# p1s.net
KiCad netlist of a schematic drawn in EAGLE
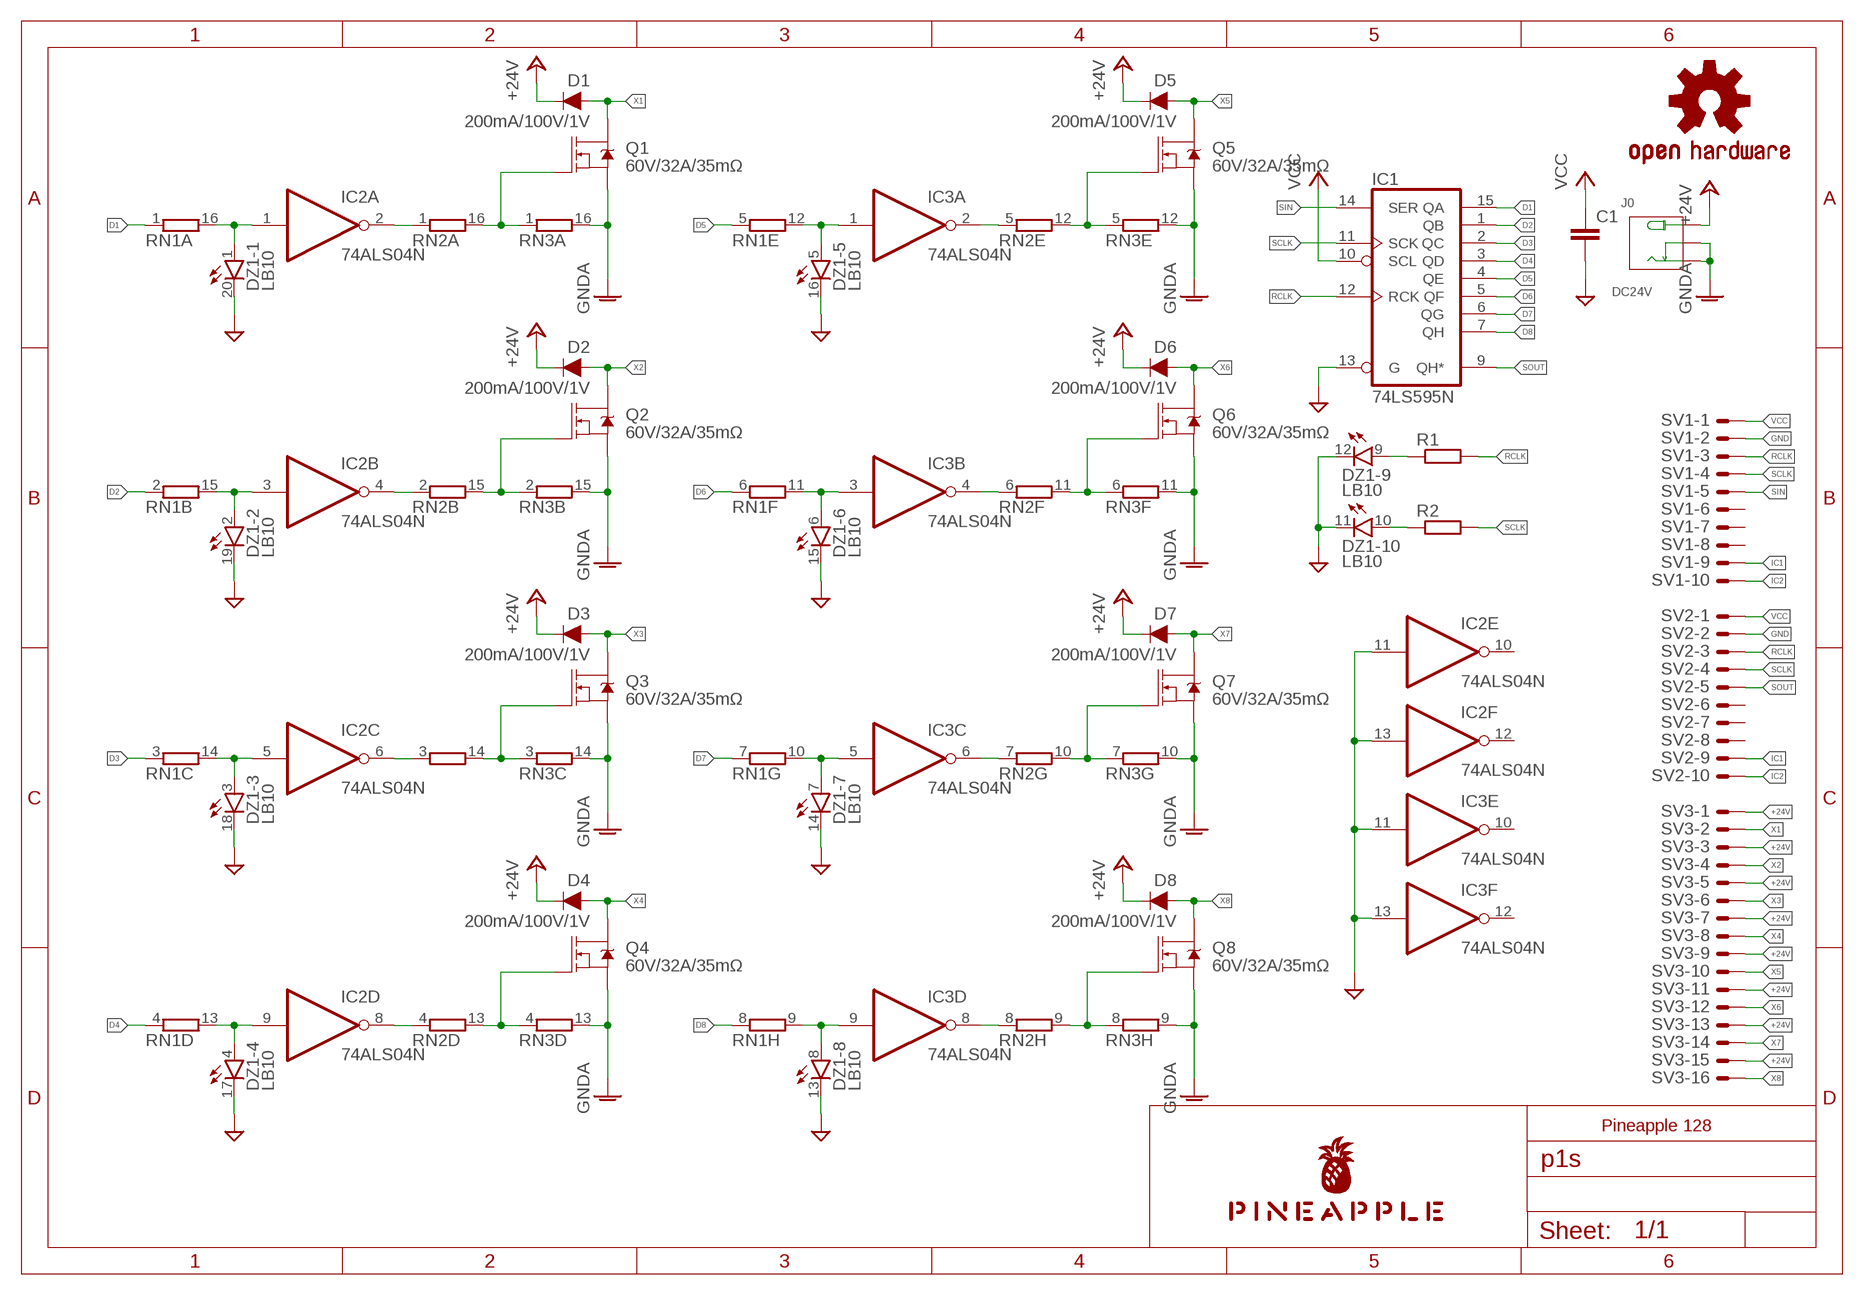
[diagram p0: schematic, sheet 1]

(export (version "E")
  (design (tool "Eeschema 10.0.6"))
  (components
    (comp (ref "C1")
      (value "C-EU025-024X044")
      (footprint "eagle-import:C025-024X044")
      (libsource (lib "eagle-import") (part "C-EU025-024X044"))
    )
    (comp (ref "D1")
      (value "200mA/100V/1V")
      (footprint "eagle-import:DIODE-1N4148")
      (libsource (lib "eagle-import") (part "DIODE-1N4148"))
    )
    (comp (ref "D2")
      (value "200mA/100V/1V")
      (footprint "eagle-import:DIODE-1N4148")
      (libsource (lib "eagle-import") (part "DIODE-1N4148"))
    )
    (comp (ref "D3")
      (value "200mA/100V/1V")
      (footprint "eagle-import:DIODE-1N4148")
      (libsource (lib "eagle-import") (part "DIODE-1N4148"))
    )
    (comp (ref "D4")
      (value "200mA/100V/1V")
      (footprint "eagle-import:DIODE-1N4148")
      (libsource (lib "eagle-import") (part "DIODE-1N4148"))
    )
    (comp (ref "D5")
      (value "200mA/100V/1V")
      (footprint "eagle-import:DIODE-1N4148")
      (libsource (lib "eagle-import") (part "DIODE-1N4148"))
    )
    (comp (ref "D6")
      (value "200mA/100V/1V")
      (footprint "eagle-import:DIODE-1N4148")
      (libsource (lib "eagle-import") (part "DIODE-1N4148"))
    )
    (comp (ref "D7")
      (value "200mA/100V/1V")
      (footprint "eagle-import:DIODE-1N4148")
      (libsource (lib "eagle-import") (part "DIODE-1N4148"))
    )
    (comp (ref "D8")
      (value "200mA/100V/1V")
      (footprint "eagle-import:DIODE-1N4148")
      (libsource (lib "eagle-import") (part "DIODE-1N4148"))
    )
    (comp (ref "DZ1")
      (value "LB10")
      (footprint "eagle-import:LB10")
      (libsource (lib "eagle-import") (part "LB10"))
    )
    (comp (ref "IC1")
      (value "74LS595N")
      (footprint "eagle-import:DIL16")
      (libsource (lib "eagle-import") (part "74595NLS"))
    )
    (comp (ref "IC2")
      (value "74ALS04N")
      (footprint "eagle-import:DIL14")
      (libsource (lib "eagle-import") (part "7404NALS"))
    )
    (comp (ref "IC3")
      (value "74ALS04N")
      (footprint "eagle-import:DIL14")
      (libsource (lib "eagle-import") (part "7404NALS"))
    )
    (comp (ref "J0")
      (value "DC24V")
      (footprint "eagle-import:3P-L14.2_W11.0_H9.0MM")
      (libsource (lib "eagle-import") (part "JACK-DC-005'DC-005'"))
    )
    (comp (ref "LOGO1")
      (value "OSHW-LOGOS-COPPER")
      (footprint "eagle-import:OSHW-LOGO-S_COPPER")
      (libsource (lib "eagle-import") (part "OSHW-LOGOS-COPPER"))
    )
    (comp (ref "Q1")
      (value "60V/32A/35mΩ")
      (footprint "eagle-import:TO220V")
      (libsource (lib "eagle-import") (part "MOSFET-NCH-FQP30N06L"))
    )
    (comp (ref "Q2")
      (value "60V/32A/35mΩ")
      (footprint "eagle-import:TO220V")
      (libsource (lib "eagle-import") (part "MOSFET-NCH-FQP30N06L"))
    )
    (comp (ref "Q3")
      (value "60V/32A/35mΩ")
      (footprint "eagle-import:TO220V")
      (libsource (lib "eagle-import") (part "MOSFET-NCH-FQP30N06L"))
    )
    (comp (ref "Q4")
      (value "60V/32A/35mΩ")
      (footprint "eagle-import:TO220V")
      (libsource (lib "eagle-import") (part "MOSFET-NCH-FQP30N06L"))
    )
    (comp (ref "Q5")
      (value "60V/32A/35mΩ")
      (footprint "eagle-import:TO220V")
      (libsource (lib "eagle-import") (part "MOSFET-NCH-FQP30N06L"))
    )
    (comp (ref "Q6")
      (value "60V/32A/35mΩ")
      (footprint "eagle-import:TO220V")
      (libsource (lib "eagle-import") (part "MOSFET-NCH-FQP30N06L"))
    )
    (comp (ref "Q7")
      (value "60V/32A/35mΩ")
      (footprint "eagle-import:TO220V")
      (libsource (lib "eagle-import") (part "MOSFET-NCH-FQP30N06L"))
    )
    (comp (ref "Q8")
      (value "60V/32A/35mΩ")
      (footprint "eagle-import:TO220V")
      (libsource (lib "eagle-import") (part "MOSFET-NCH-FQP30N06L"))
    )
    (comp (ref "R1")
      (value "R-EU_0204/5")
      (footprint "eagle-import:0204_5")
      (libsource (lib "eagle-import") (part "R-EU_0204/5"))
    )
    (comp (ref "R2")
      (value "R-EU_0204/5")
      (footprint "eagle-import:0204_5")
      (libsource (lib "eagle-import") (part "R-EU_0204/5"))
    )
    (comp (ref "RN1")
      (value "8R-N")
      (footprint "eagle-import:DIL16")
      (libsource (lib "eagle-import") (part "8R-N"))
    )
    (comp (ref "RN2")
      (value "8R-N")
      (footprint "eagle-import:DIL16")
      (libsource (lib "eagle-import") (part "8R-N"))
    )
    (comp (ref "RN3")
      (value "8R-N")
      (footprint "eagle-import:DIL16")
      (libsource (lib "eagle-import") (part "8R-N"))
    )
    (comp (ref "SV1")
      (value "ML10LE")
      (footprint "eagle-import:ML10L")
      (libsource (lib "eagle-import") (part "ML10LE"))
    )
    (comp (ref "SV2")
      (value "ML10LE")
      (footprint "eagle-import:ML10L")
      (libsource (lib "eagle-import") (part "ML10LE"))
    )
    (comp (ref "SV3")
      (value "ML16LE")
      (footprint "eagle-import:ML16L")
      (libsource (lib "eagle-import") (part "ML16LE"))
    )
    (comp (ref "U$1")
      (value "PINEAPPLE450_SILK")
      (footprint "eagle-import:PINEAPPLE450_SILK")
      (libsource (lib "eagle-import") (part "PINEAPPLE450_SILK"))
    )
  )
  (nets
    (net (code "1") (name "+24V") (class "Default")
      (node (ref "D1") (pin "C") (pinfunction "C_C") (pintype "passive"))
      (node (ref "D2") (pin "C") (pinfunction "C_C") (pintype "passive"))
      (node (ref "D3") (pin "C") (pinfunction "C_C") (pintype "passive"))
      (node (ref "D4") (pin "C") (pinfunction "C_C") (pintype "passive"))
      (node (ref "D5") (pin "C") (pinfunction "C_C") (pintype "passive"))
      (node (ref "D6") (pin "C") (pinfunction "C_C") (pintype "passive"))
      (node (ref "D7") (pin "C") (pinfunction "C_C") (pintype "passive"))
      (node (ref "D8") (pin "C") (pinfunction "C_C") (pintype "passive"))
      (node (ref "J0") (pin "+") (pinfunction "+_+") (pintype "bidirectional"))
      (node (ref "SV3") (pin "1") (pinfunction "S_1") (pintype "passive"))
      (node (ref "SV3") (pin "11") (pinfunction "S_11") (pintype "passive"))
      (node (ref "SV3") (pin "13") (pinfunction "S_13") (pintype "passive"))
      (node (ref "SV3") (pin "15") (pinfunction "S_15") (pintype "passive"))
      (node (ref "SV3") (pin "3") (pinfunction "S_3") (pintype "passive"))
      (node (ref "SV3") (pin "5") (pinfunction "S_5") (pintype "passive"))
      (node (ref "SV3") (pin "7") (pinfunction "S_7") (pintype "passive"))
      (node (ref "SV3") (pin "9") (pinfunction "S_9") (pintype "passive"))
    )
    (net (code "2") (name "D1") (class "Default")
      (node (ref "IC1") (pin "15") (pinfunction "QA_15") (pintype "tri_state"))
      (node (ref "RN1") (pin "1") (pinfunction "1_1") (pintype "passive"))
    )
    (net (code "3") (name "D2") (class "Default")
      (node (ref "IC1") (pin "1") (pinfunction "QB_1") (pintype "tri_state"))
      (node (ref "RN1") (pin "2") (pinfunction "1_2") (pintype "passive"))
    )
    (net (code "4") (name "D3") (class "Default")
      (node (ref "IC1") (pin "2") (pinfunction "QC_2") (pintype "tri_state"))
      (node (ref "RN1") (pin "3") (pinfunction "1_3") (pintype "passive"))
    )
    (net (code "5") (name "D4") (class "Default")
      (node (ref "IC1") (pin "3") (pinfunction "QD_3") (pintype "tri_state"))
      (node (ref "RN1") (pin "4") (pinfunction "1_4") (pintype "passive"))
    )
    (net (code "6") (name "D5") (class "Default")
      (node (ref "IC1") (pin "4") (pinfunction "QE_4") (pintype "tri_state"))
      (node (ref "RN1") (pin "5") (pinfunction "1_5") (pintype "passive"))
    )
    (net (code "7") (name "D6") (class "Default")
      (node (ref "IC1") (pin "5") (pinfunction "QF_5") (pintype "tri_state"))
      (node (ref "RN1") (pin "6") (pinfunction "1_6") (pintype "passive"))
    )
    (net (code "8") (name "D7") (class "Default")
      (node (ref "IC1") (pin "6") (pinfunction "QG_6") (pintype "tri_state"))
      (node (ref "RN1") (pin "7") (pinfunction "1_7") (pintype "passive"))
    )
    (net (code "9") (name "D8") (class "Default")
      (node (ref "IC1") (pin "7") (pinfunction "QH_7") (pintype "tri_state"))
      (node (ref "RN1") (pin "8") (pinfunction "1_8") (pintype "passive"))
    )
    (net (code "10") (name "GND") (class "Default")
      (node (ref "C1") (pin "2") (pinfunction "2_2") (pintype "passive"))
      (node (ref "DZ1") (pin "11") (pinfunction "C_11") (pintype "passive"))
      (node (ref "DZ1") (pin "12") (pinfunction "C_12") (pintype "passive"))
      (node (ref "DZ1") (pin "13") (pinfunction "C_13") (pintype "passive"))
      (node (ref "DZ1") (pin "14") (pinfunction "C_14") (pintype "passive"))
      (node (ref "DZ1") (pin "15") (pinfunction "C_15") (pintype "passive"))
      (node (ref "DZ1") (pin "16") (pinfunction "C_16") (pintype "passive"))
      (node (ref "DZ1") (pin "17") (pinfunction "C_17") (pintype "passive"))
      (node (ref "DZ1") (pin "18") (pinfunction "C_18") (pintype "passive"))
      (node (ref "DZ1") (pin "19") (pinfunction "C_19") (pintype "passive"))
      (node (ref "DZ1") (pin "20") (pinfunction "C_20") (pintype "passive"))
      (node (ref "IC1") (pin "13") (pinfunction "G_13") (pintype "input"))
      (node (ref "IC2") (pin "11") (pinfunction "I_11") (pintype "input"))
      (node (ref "IC2") (pin "13") (pinfunction "I_13") (pintype "input"))
      (node (ref "IC3") (pin "11") (pinfunction "I_11") (pintype "input"))
      (node (ref "IC3") (pin "13") (pinfunction "I_13") (pintype "input"))
      (node (ref "SV1") (pin "2") (pinfunction "S_2") (pintype "passive"))
      (node (ref "SV2") (pin "2") (pinfunction "S_2") (pintype "passive"))
    )
    (net (code "11") (name "GNDA") (class "Default")
      (node (ref "J0") (pin "-1") (pinfunction "-_-1") (pintype "bidirectional"))
      (node (ref "J0") (pin "-2") (pinfunction "CDN_-2") (pintype "bidirectional"))
      (node (ref "Q1") (pin "3") (pinfunction "S_3") (pintype "bidirectional"))
      (node (ref "Q2") (pin "3") (pinfunction "S_3") (pintype "bidirectional"))
      (node (ref "Q3") (pin "3") (pinfunction "S_3") (pintype "bidirectional"))
      (node (ref "Q4") (pin "3") (pinfunction "S_3") (pintype "bidirectional"))
      (node (ref "Q5") (pin "3") (pinfunction "S_3") (pintype "bidirectional"))
      (node (ref "Q6") (pin "3") (pinfunction "S_3") (pintype "bidirectional"))
      (node (ref "Q7") (pin "3") (pinfunction "S_3") (pintype "bidirectional"))
      (node (ref "Q8") (pin "3") (pinfunction "S_3") (pintype "bidirectional"))
      (node (ref "RN3") (pin "10") (pinfunction "2_10") (pintype "passive"))
      (node (ref "RN3") (pin "11") (pinfunction "2_11") (pintype "passive"))
      (node (ref "RN3") (pin "12") (pinfunction "2_12") (pintype "passive"))
      (node (ref "RN3") (pin "13") (pinfunction "2_13") (pintype "passive"))
      (node (ref "RN3") (pin "14") (pinfunction "2_14") (pintype "passive"))
      (node (ref "RN3") (pin "15") (pinfunction "2_15") (pintype "passive"))
      (node (ref "RN3") (pin "16") (pinfunction "2_16") (pintype "passive"))
      (node (ref "RN3") (pin "9") (pinfunction "2_9") (pintype "passive"))
    )
    (net (code "12") (name "IC1") (class "Default")
      (node (ref "SV1") (pin "9") (pinfunction "S_9") (pintype "passive"))
      (node (ref "SV2") (pin "9") (pinfunction "S_9") (pintype "passive"))
    )
    (net (code "13") (name "IC2") (class "Default")
      (node (ref "SV1") (pin "10") (pinfunction "S_10") (pintype "passive"))
      (node (ref "SV2") (pin "10") (pinfunction "S_10") (pintype "passive"))
    )
    (net (code "14") (name "Net-(DZ1A-A)") (class "Default")
      (node (ref "DZ1") (pin "1") (pinfunction "A_1") (pintype "passive"))
      (node (ref "IC2") (pin "1") (pinfunction "I_1") (pintype "input"))
      (node (ref "RN1") (pin "16") (pinfunction "2_16") (pintype "passive"))
    )
    (net (code "15") (name "Net-(DZ1B-A)") (class "Default")
      (node (ref "DZ1") (pin "10") (pinfunction "A_10") (pintype "passive"))
      (node (ref "R2") (pin "1") (pinfunction "1_1") (pintype "passive"))
    )
    (net (code "16") (name "Net-(DZ1C-A)") (class "Default")
      (node (ref "DZ1") (pin "2") (pinfunction "A_2") (pintype "passive"))
      (node (ref "IC2") (pin "3") (pinfunction "I_3") (pintype "input"))
      (node (ref "RN1") (pin "15") (pinfunction "2_15") (pintype "passive"))
    )
    (net (code "17") (name "Net-(DZ1D-A)") (class "Default")
      (node (ref "DZ1") (pin "3") (pinfunction "A_3") (pintype "passive"))
      (node (ref "IC2") (pin "5") (pinfunction "I_5") (pintype "input"))
      (node (ref "RN1") (pin "14") (pinfunction "2_14") (pintype "passive"))
    )
    (net (code "18") (name "Net-(DZ1E-A)") (class "Default")
      (node (ref "DZ1") (pin "4") (pinfunction "A_4") (pintype "passive"))
      (node (ref "IC2") (pin "9") (pinfunction "I_9") (pintype "input"))
      (node (ref "RN1") (pin "13") (pinfunction "2_13") (pintype "passive"))
    )
    (net (code "19") (name "Net-(DZ1F-A)") (class "Default")
      (node (ref "DZ1") (pin "5") (pinfunction "A_5") (pintype "passive"))
      (node (ref "IC3") (pin "1") (pinfunction "I_1") (pintype "input"))
      (node (ref "RN1") (pin "12") (pinfunction "2_12") (pintype "passive"))
    )
    (net (code "20") (name "Net-(DZ1G-A)") (class "Default")
      (node (ref "DZ1") (pin "6") (pinfunction "A_6") (pintype "passive"))
      (node (ref "IC3") (pin "3") (pinfunction "I_3") (pintype "input"))
      (node (ref "RN1") (pin "11") (pinfunction "2_11") (pintype "passive"))
    )
    (net (code "21") (name "Net-(DZ1H-A)") (class "Default")
      (node (ref "DZ1") (pin "7") (pinfunction "A_7") (pintype "passive"))
      (node (ref "IC3") (pin "5") (pinfunction "I_5") (pintype "input"))
      (node (ref "RN1") (pin "10") (pinfunction "2_10") (pintype "passive"))
    )
    (net (code "22") (name "Net-(DZ1I-A)") (class "Default")
      (node (ref "DZ1") (pin "8") (pinfunction "A_8") (pintype "passive"))
      (node (ref "IC3") (pin "9") (pinfunction "I_9") (pintype "input"))
      (node (ref "RN1") (pin "9") (pinfunction "2_9") (pintype "passive"))
    )
    (net (code "23") (name "Net-(DZ1J-A)") (class "Default")
      (node (ref "DZ1") (pin "9") (pinfunction "A_9") (pintype "passive"))
      (node (ref "R1") (pin "1") (pinfunction "1_1") (pintype "passive"))
    )
    (net (code "24") (name "Net-(IC2A-O)") (class "Default")
      (node (ref "IC2") (pin "2") (pinfunction "O_2") (pintype "output"))
      (node (ref "RN2") (pin "1") (pinfunction "1_1") (pintype "passive"))
    )
    (net (code "25") (name "Net-(IC2B-O)") (class "Default")
      (node (ref "IC2") (pin "4") (pinfunction "O_4") (pintype "output"))
      (node (ref "RN2") (pin "2") (pinfunction "1_2") (pintype "passive"))
    )
    (net (code "26") (name "Net-(IC2C-O)") (class "Default")
      (node (ref "IC2") (pin "6") (pinfunction "O_6") (pintype "output"))
      (node (ref "RN2") (pin "3") (pinfunction "1_3") (pintype "passive"))
    )
    (net (code "27") (name "Net-(IC2D-O)") (class "Default")
      (node (ref "IC2") (pin "8") (pinfunction "O_8") (pintype "output"))
      (node (ref "RN2") (pin "4") (pinfunction "1_4") (pintype "passive"))
    )
    (net (code "28") (name "Net-(IC3A-O)") (class "Default")
      (node (ref "IC3") (pin "2") (pinfunction "O_2") (pintype "output"))
      (node (ref "RN2") (pin "5") (pinfunction "1_5") (pintype "passive"))
    )
    (net (code "29") (name "Net-(IC3B-O)") (class "Default")
      (node (ref "IC3") (pin "4") (pinfunction "O_4") (pintype "output"))
      (node (ref "RN2") (pin "6") (pinfunction "1_6") (pintype "passive"))
    )
    (net (code "30") (name "Net-(IC3C-O)") (class "Default")
      (node (ref "IC3") (pin "6") (pinfunction "O_6") (pintype "output"))
      (node (ref "RN2") (pin "7") (pinfunction "1_7") (pintype "passive"))
    )
    (net (code "31") (name "Net-(IC3D-O)") (class "Default")
      (node (ref "IC3") (pin "8") (pinfunction "O_8") (pintype "output"))
      (node (ref "RN2") (pin "8") (pinfunction "1_8") (pintype "passive"))
    )
    (net (code "32") (name "Net-(Q1-G)") (class "Default")
      (node (ref "Q1") (pin "1") (pinfunction "G_1") (pintype "bidirectional"))
      (node (ref "RN2") (pin "16") (pinfunction "2_16") (pintype "passive"))
      (node (ref "RN3") (pin "1") (pinfunction "1_1") (pintype "passive"))
    )
    (net (code "33") (name "Net-(Q2-G)") (class "Default")
      (node (ref "Q2") (pin "1") (pinfunction "G_1") (pintype "bidirectional"))
      (node (ref "RN2") (pin "15") (pinfunction "2_15") (pintype "passive"))
      (node (ref "RN3") (pin "2") (pinfunction "1_2") (pintype "passive"))
    )
    (net (code "34") (name "Net-(Q3-G)") (class "Default")
      (node (ref "Q3") (pin "1") (pinfunction "G_1") (pintype "bidirectional"))
      (node (ref "RN2") (pin "14") (pinfunction "2_14") (pintype "passive"))
      (node (ref "RN3") (pin "3") (pinfunction "1_3") (pintype "passive"))
    )
    (net (code "35") (name "Net-(Q4-G)") (class "Default")
      (node (ref "Q4") (pin "1") (pinfunction "G_1") (pintype "bidirectional"))
      (node (ref "RN2") (pin "13") (pinfunction "2_13") (pintype "passive"))
      (node (ref "RN3") (pin "4") (pinfunction "1_4") (pintype "passive"))
    )
    (net (code "36") (name "Net-(Q5-G)") (class "Default")
      (node (ref "Q5") (pin "1") (pinfunction "G_1") (pintype "bidirectional"))
      (node (ref "RN2") (pin "12") (pinfunction "2_12") (pintype "passive"))
      (node (ref "RN3") (pin "5") (pinfunction "1_5") (pintype "passive"))
    )
    (net (code "37") (name "Net-(Q6-G)") (class "Default")
      (node (ref "Q6") (pin "1") (pinfunction "G_1") (pintype "bidirectional"))
      (node (ref "RN2") (pin "11") (pinfunction "2_11") (pintype "passive"))
      (node (ref "RN3") (pin "6") (pinfunction "1_6") (pintype "passive"))
    )
    (net (code "38") (name "Net-(Q7-G)") (class "Default")
      (node (ref "Q7") (pin "1") (pinfunction "G_1") (pintype "bidirectional"))
      (node (ref "RN2") (pin "10") (pinfunction "2_10") (pintype "passive"))
      (node (ref "RN3") (pin "7") (pinfunction "1_7") (pintype "passive"))
    )
    (net (code "39") (name "Net-(Q8-G)") (class "Default")
      (node (ref "Q8") (pin "1") (pinfunction "G_1") (pintype "bidirectional"))
      (node (ref "RN2") (pin "9") (pinfunction "2_9") (pintype "passive"))
      (node (ref "RN3") (pin "8") (pinfunction "1_8") (pintype "passive"))
    )
    (net (code "40") (name "RCLK") (class "Default")
      (node (ref "IC1") (pin "12") (pinfunction "RCK_12") (pintype "input"))
      (node (ref "R1") (pin "2") (pinfunction "2_2") (pintype "passive"))
      (node (ref "SV1") (pin "3") (pinfunction "S_3") (pintype "passive"))
      (node (ref "SV2") (pin "3") (pinfunction "S_3") (pintype "passive"))
    )
    (net (code "41") (name "SCLK") (class "Default")
      (node (ref "IC1") (pin "11") (pinfunction "SCK_11") (pintype "input"))
      (node (ref "R2") (pin "2") (pinfunction "2_2") (pintype "passive"))
      (node (ref "SV1") (pin "4") (pinfunction "S_4") (pintype "passive"))
      (node (ref "SV2") (pin "4") (pinfunction "S_4") (pintype "passive"))
    )
    (net (code "42") (name "SIN") (class "Default")
      (node (ref "IC1") (pin "14") (pinfunction "SER_14") (pintype "input"))
      (node (ref "SV1") (pin "5") (pinfunction "S_5") (pintype "passive"))
    )
    (net (code "43") (name "SOUT") (class "Default")
      (node (ref "IC1") (pin "9") (pinfunction "QH*_9") (pintype "tri_state"))
      (node (ref "SV2") (pin "5") (pinfunction "S_5") (pintype "passive"))
    )
    (net (code "44") (name "VCC") (class "Default")
      (node (ref "C1") (pin "1") (pinfunction "1_1") (pintype "passive"))
      (node (ref "IC1") (pin "10") (pinfunction "SCL_10") (pintype "input"))
      (node (ref "SV1") (pin "1") (pinfunction "S_1") (pintype "passive"))
      (node (ref "SV2") (pin "1") (pinfunction "S_1") (pintype "passive"))
    )
    (net (code "45") (name "X1") (class "Default")
      (node (ref "D1") (pin "A") (pinfunction "A_A") (pintype "passive"))
      (node (ref "Q1") (pin "2") (pinfunction "D_2") (pintype "bidirectional"))
      (node (ref "SV3") (pin "2") (pinfunction "S_2") (pintype "passive"))
    )
    (net (code "46") (name "X2") (class "Default")
      (node (ref "D2") (pin "A") (pinfunction "A_A") (pintype "passive"))
      (node (ref "Q2") (pin "2") (pinfunction "D_2") (pintype "bidirectional"))
      (node (ref "SV3") (pin "4") (pinfunction "S_4") (pintype "passive"))
    )
    (net (code "47") (name "X3") (class "Default")
      (node (ref "D3") (pin "A") (pinfunction "A_A") (pintype "passive"))
      (node (ref "Q3") (pin "2") (pinfunction "D_2") (pintype "bidirectional"))
      (node (ref "SV3") (pin "6") (pinfunction "S_6") (pintype "passive"))
    )
    (net (code "48") (name "X4") (class "Default")
      (node (ref "D4") (pin "A") (pinfunction "A_A") (pintype "passive"))
      (node (ref "Q4") (pin "2") (pinfunction "D_2") (pintype "bidirectional"))
      (node (ref "SV3") (pin "8") (pinfunction "S_8") (pintype "passive"))
    )
    (net (code "49") (name "X5") (class "Default")
      (node (ref "D5") (pin "A") (pinfunction "A_A") (pintype "passive"))
      (node (ref "Q5") (pin "2") (pinfunction "D_2") (pintype "bidirectional"))
      (node (ref "SV3") (pin "10") (pinfunction "S_10") (pintype "passive"))
    )
    (net (code "50") (name "X6") (class "Default")
      (node (ref "D6") (pin "A") (pinfunction "A_A") (pintype "passive"))
      (node (ref "Q6") (pin "2") (pinfunction "D_2") (pintype "bidirectional"))
      (node (ref "SV3") (pin "12") (pinfunction "S_12") (pintype "passive"))
    )
    (net (code "51") (name "X7") (class "Default")
      (node (ref "D7") (pin "A") (pinfunction "A_A") (pintype "passive"))
      (node (ref "Q7") (pin "2") (pinfunction "D_2") (pintype "bidirectional"))
      (node (ref "SV3") (pin "14") (pinfunction "S_14") (pintype "passive"))
    )
    (net (code "52") (name "X8") (class "Default")
      (node (ref "D8") (pin "A") (pinfunction "A_A") (pintype "passive"))
      (node (ref "Q8") (pin "2") (pinfunction "D_2") (pintype "bidirectional"))
      (node (ref "SV3") (pin "16") (pinfunction "S_16") (pintype "passive"))
    )
    (net (code "53") (name "unconnected-(IC2E-O-Pad10)") (class "Default")
      (node (ref "IC2") (pin "10") (pinfunction "O_10") (pintype "output"))
    )
    (net (code "54") (name "unconnected-(IC2F-O-Pad12)") (class "Default")
      (node (ref "IC2") (pin "12") (pinfunction "O_12") (pintype "output"))
    )
    (net (code "55") (name "unconnected-(IC3E-O-Pad10)") (class "Default")
      (node (ref "IC3") (pin "10") (pinfunction "O_10") (pintype "output"))
    )
    (net (code "56") (name "unconnected-(IC3F-O-Pad12)") (class "Default")
      (node (ref "IC3") (pin "12") (pinfunction "O_12") (pintype "output"))
    )
    (net (code "57") (name "unconnected-(SV1G-S-Pad6)") (class "Default")
      (node (ref "SV1") (pin "6") (pinfunction "S_6") (pintype "passive"))
    )
    (net (code "58") (name "unconnected-(SV1H-S-Pad7)") (class "Default")
      (node (ref "SV1") (pin "7") (pinfunction "S_7") (pintype "passive"))
    )
    (net (code "59") (name "unconnected-(SV1I-S-Pad8)") (class "Default")
      (node (ref "SV1") (pin "8") (pinfunction "S_8") (pintype "passive"))
    )
    (net (code "60") (name "unconnected-(SV2G-S-Pad6)") (class "Default")
      (node (ref "SV2") (pin "6") (pinfunction "S_6") (pintype "passive"))
    )
    (net (code "61") (name "unconnected-(SV2H-S-Pad7)") (class "Default")
      (node (ref "SV2") (pin "7") (pinfunction "S_7") (pintype "passive"))
    )
    (net (code "62") (name "unconnected-(SV2I-S-Pad8)") (class "Default")
      (node (ref "SV2") (pin "8") (pinfunction "S_8") (pintype "passive"))
    )
  )
)
